# Power_5vto3_3_MIC5205.net
KiCad netlist of a schematic drawn in EAGLE
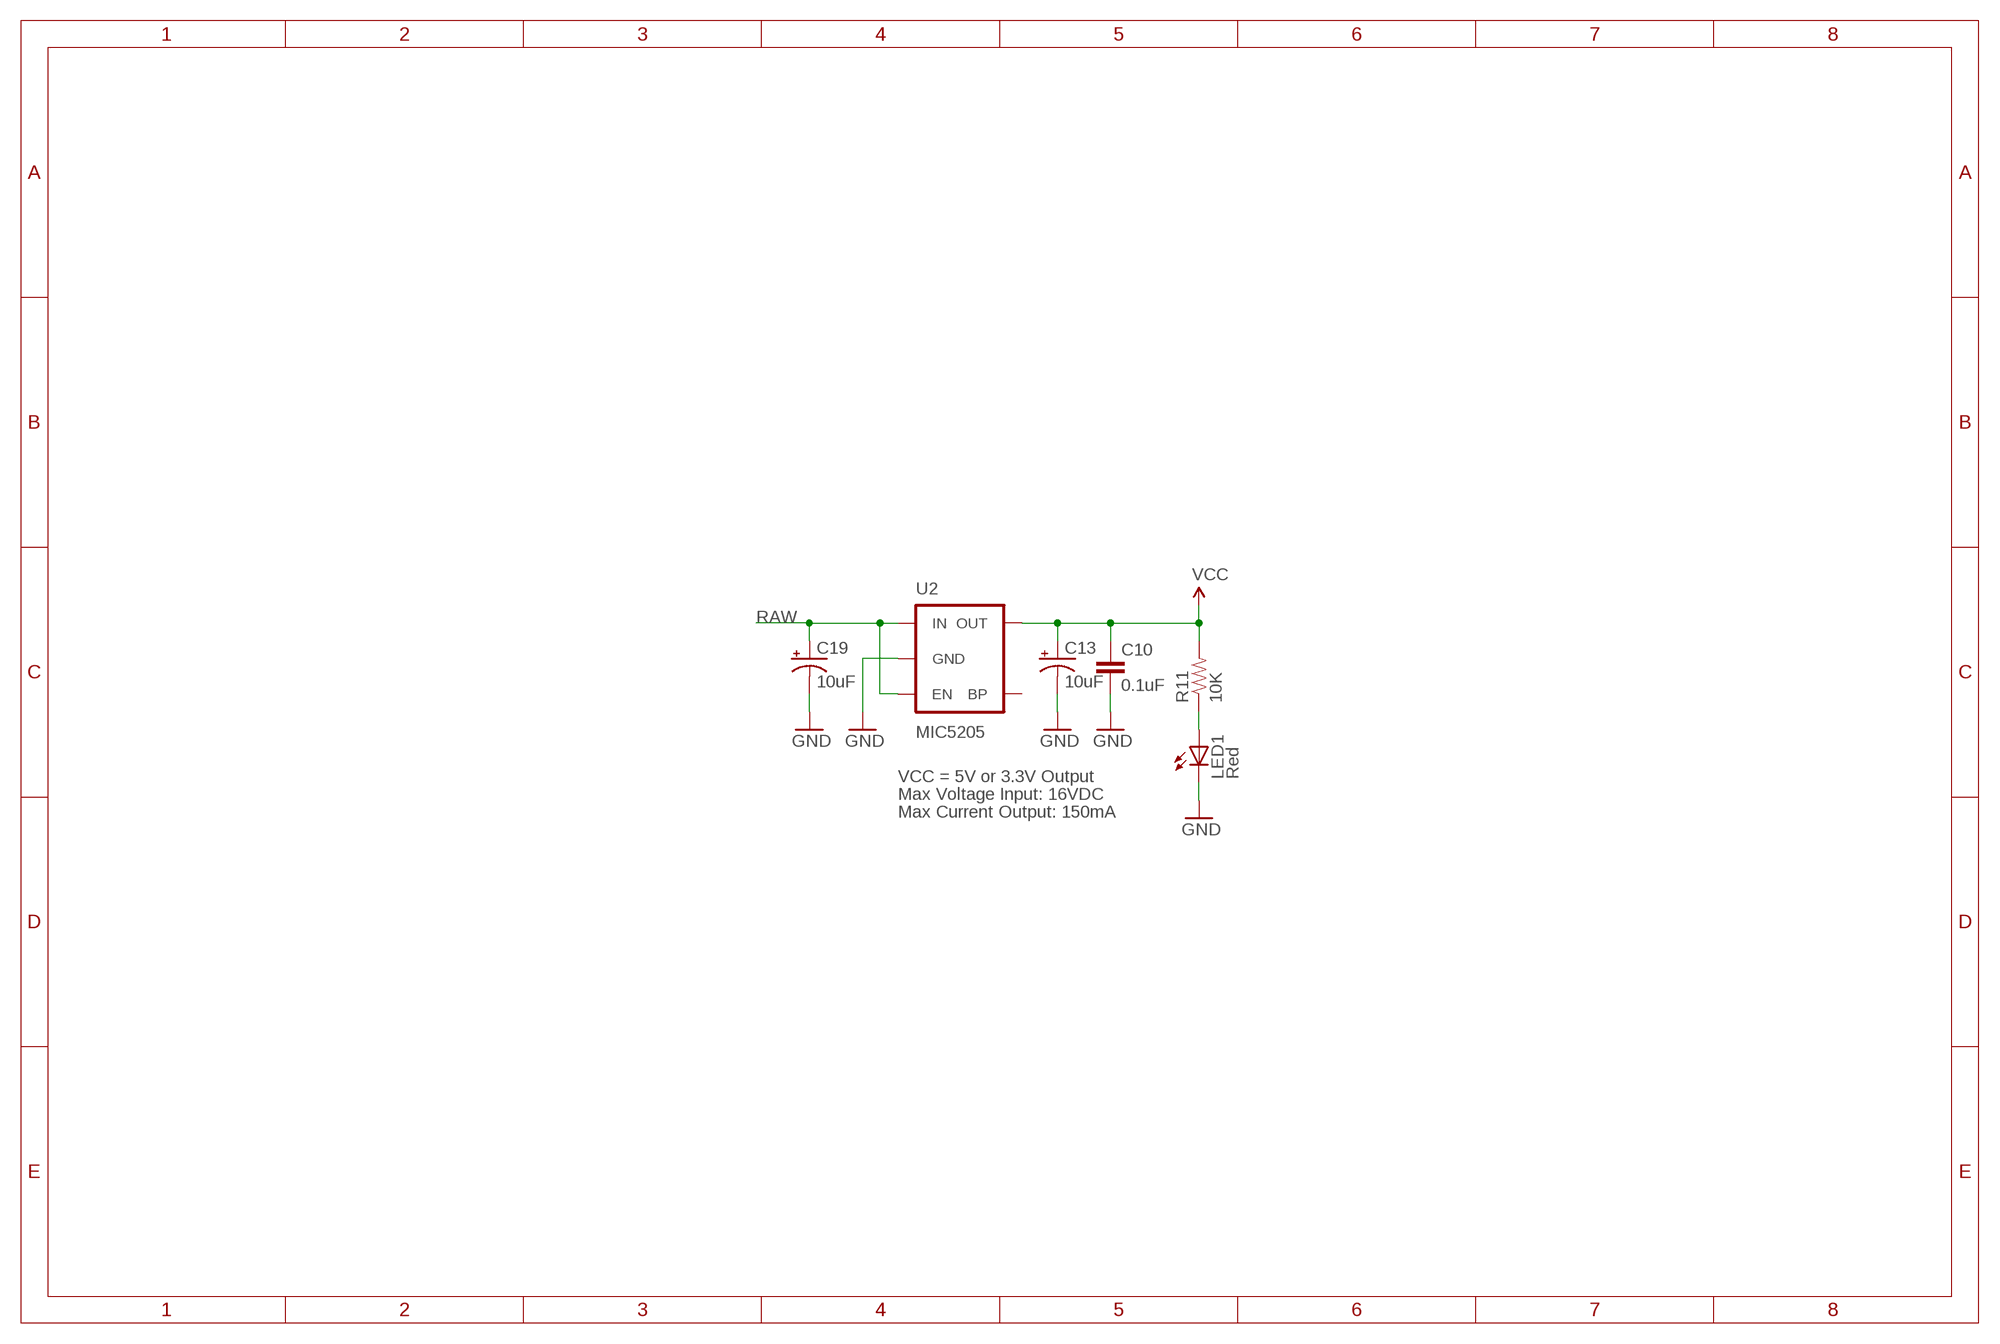
[diagram p0: schematic, sheet 1]

(export (version "E")
  (design (tool "Eeschema 10.0.6"))
  (components
    (comp (ref "C10")
      (value "0.1uF")
      (footprint "eagle-import:0402-CAP")
      (libsource (lib "eagle-import") (part "CAP0402-CAP"))
    )
    (comp (ref "C13")
      (value "10uF")
      (footprint "eagle-import:EIA3216")
      (libsource (lib "eagle-import") (part "CAP_POL1206"))
    )
    (comp (ref "C19")
      (value "10uF")
      (footprint "eagle-import:EIA3216")
      (libsource (lib "eagle-import") (part "CAP_POL1206"))
    )
    (comp (ref "LED1")
      (value "Red")
      (footprint "eagle-import:LED-0603")
      (libsource (lib "eagle-import") (part "LED0603"))
    )
    (comp (ref "R11")
      (value "10K")
      (footprint "eagle-import:0402-RES")
      (libsource (lib "eagle-import") (part "RESISTOR0402-RES"))
    )
    (comp (ref "U2")
      (value "MIC5205")
      (footprint "eagle-import:SOT23-5")
      (libsource (lib "eagle-import") (part "V_REG_LDOSMD"))
    )
  )
  (nets
    (net (code "1") (name "/RAW") (class "Default")
      (node (ref "C19") (pin "A") (pinfunction "+_A") (pintype "passive"))
      (node (ref "U2") (pin "1") (pinfunction "IN_1") (pintype "input"))
      (node (ref "U2") (pin "3") (pinfunction "EN_3") (pintype "input"))
    )
    (net (code "2") (name "GND") (class "Default")
      (node (ref "C10") (pin "2") (pinfunction "2_2") (pintype "passive"))
      (node (ref "C13") (pin "C") (pinfunction "-_C") (pintype "passive"))
      (node (ref "C19") (pin "C") (pinfunction "-_C") (pintype "passive"))
      (node (ref "LED1") (pin "C") (pinfunction "C_C") (pintype "passive"))
      (node (ref "U2") (pin "2") (pinfunction "GND_2") (pintype "input"))
    )
    (net (code "3") (name "Net-(LED1-PadA)") (class "Default")
      (node (ref "LED1") (pin "A") (pinfunction "A_A") (pintype "passive"))
      (node (ref "R11") (pin "1") (pinfunction "1_1") (pintype "passive"))
    )
    (net (code "4") (name "VCC") (class "Default")
      (node (ref "C10") (pin "1") (pinfunction "1_1") (pintype "passive"))
      (node (ref "C13") (pin "A") (pinfunction "+_A") (pintype "passive"))
      (node (ref "R11") (pin "2") (pinfunction "2_2") (pintype "passive"))
      (node (ref "U2") (pin "5") (pinfunction "OUT_5") (pintype "passive"))
    )
    (net (code "5") (name "unconnected-(U2-BP-Pad4)") (class "Default")
      (node (ref "U2") (pin "4") (pinfunction "BP_4") (pintype "input"))
    )
  )
)
